# controller.net
KiCad netlist of a schematic drawn in EAGLE
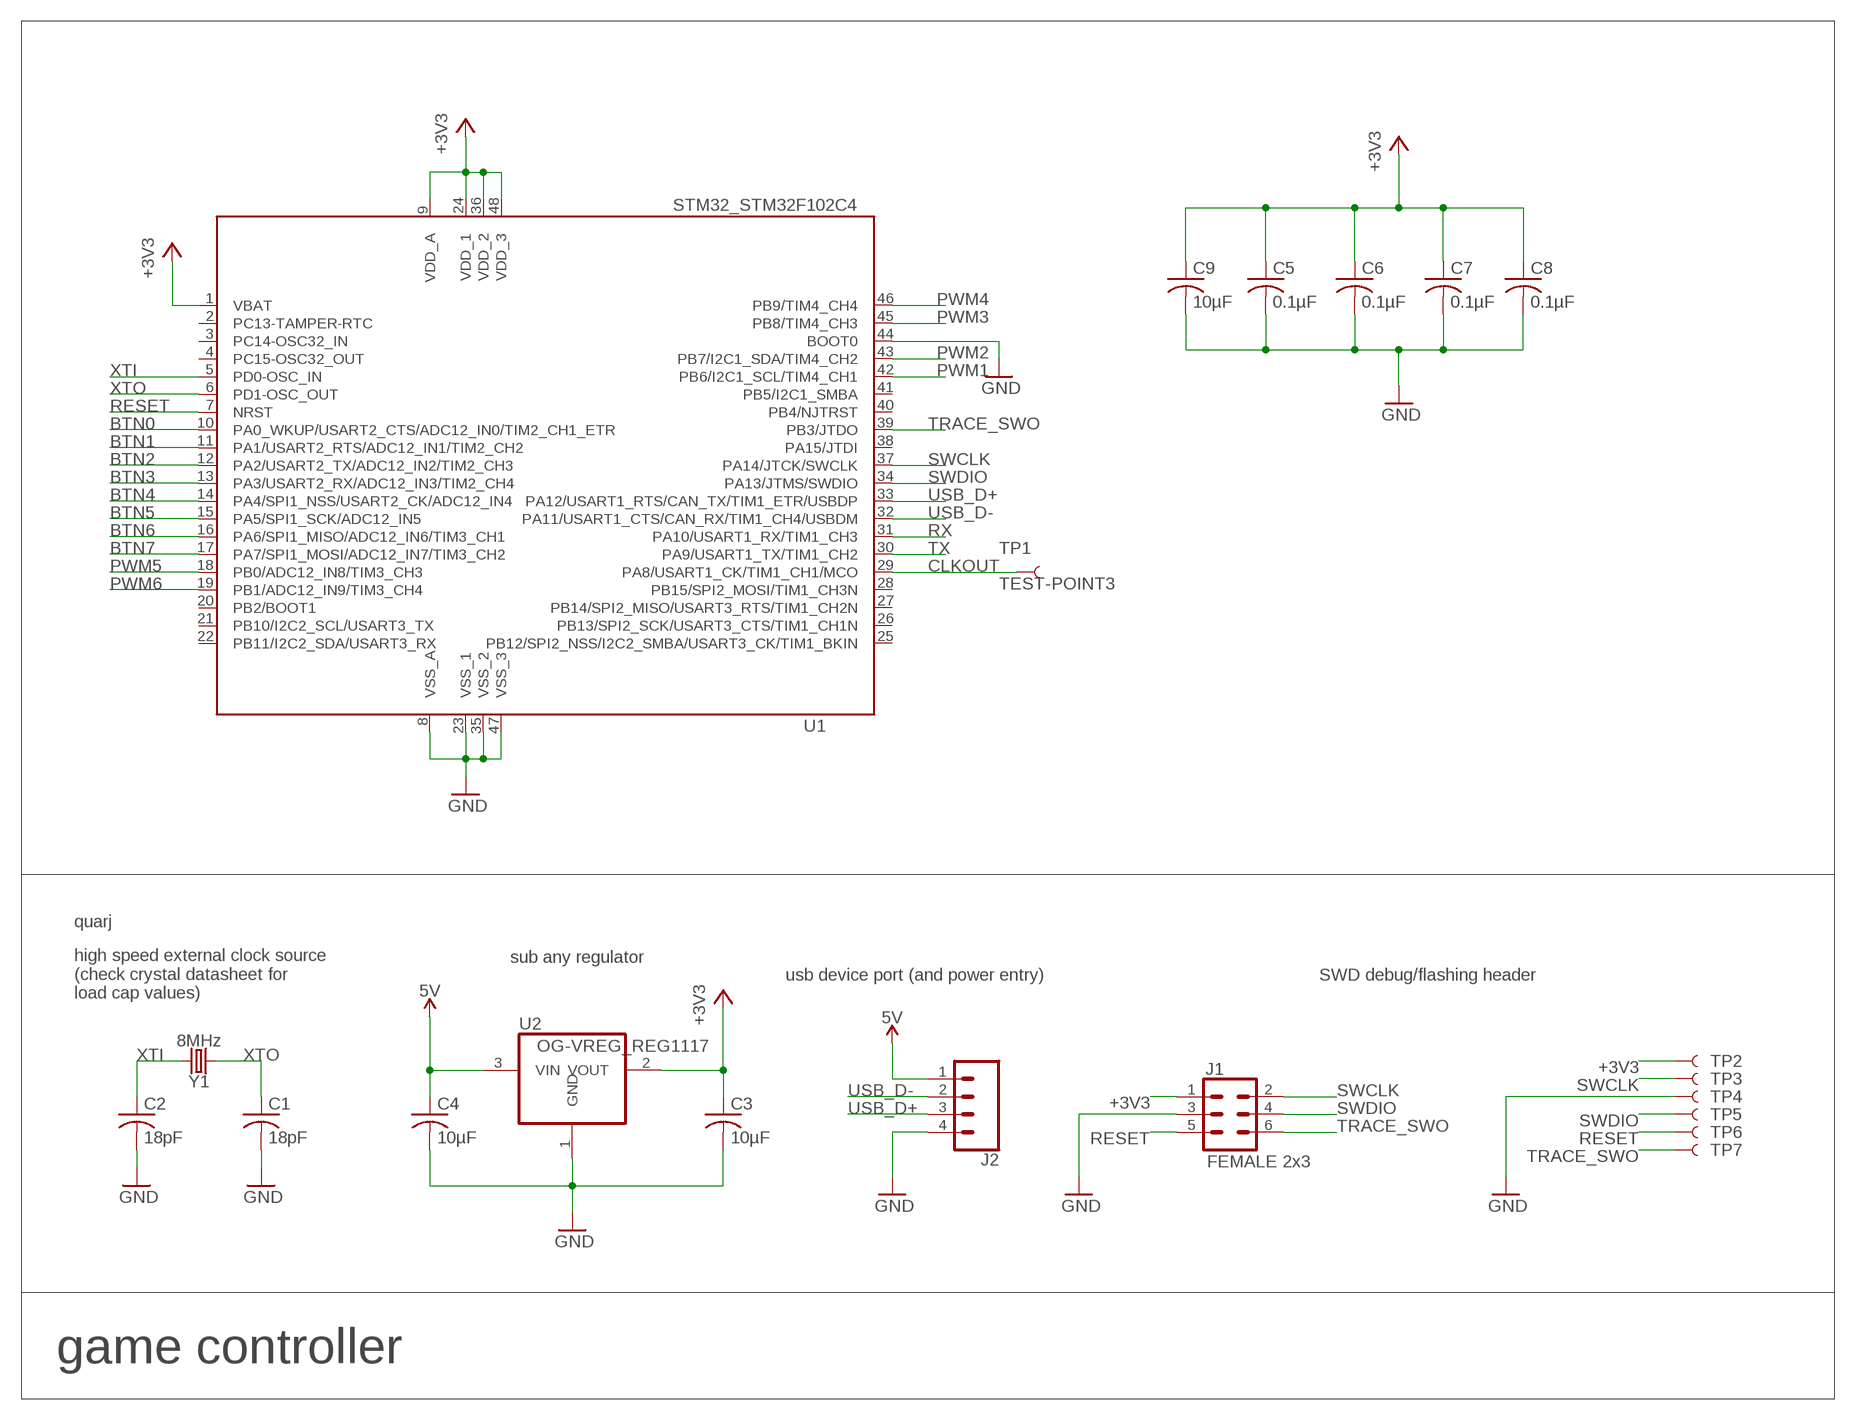
[diagram p0: schematic, sheet 1]
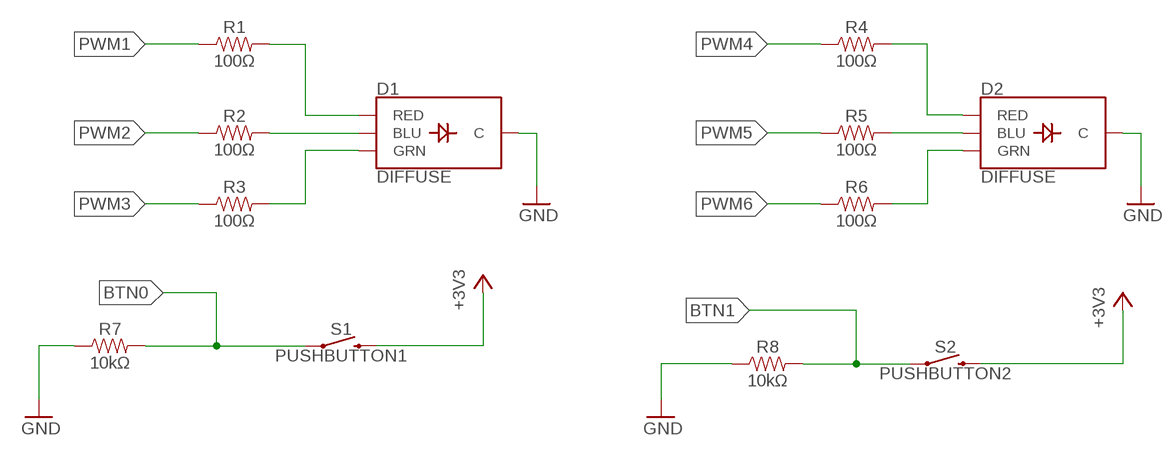
[diagram p1: schematic, sheet 2]
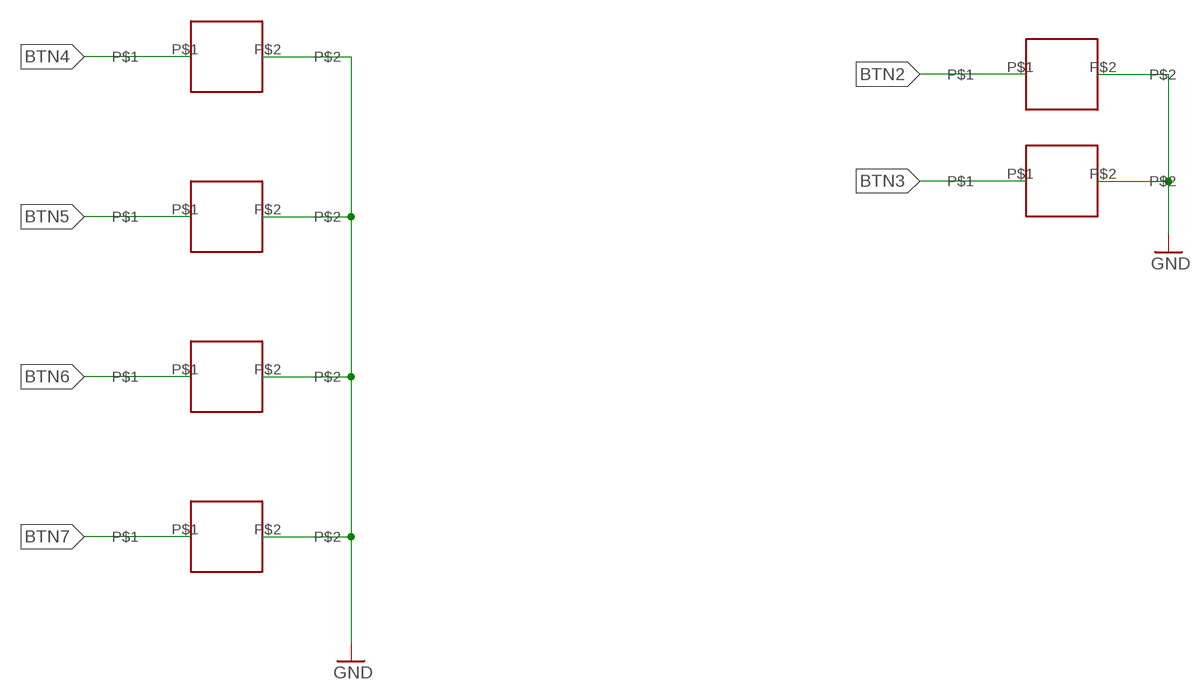
[diagram p2: schematic, sheet 3]

(export (version "E")
  (design (tool "Eeschema 10.0.6"))
  (components
    (comp (ref "A")
      (value "HYPERKIN_TOUCHPAD_CADET")
      (footprint "eagle-import:HYPERKIN_TOUCHPLATE_CADET")
      (libsource (lib "eagle-import") (part "HYPERKIN_TOUCHPAD_CADET"))
    )
    (comp (ref "B")
      (value "HYPERKIN_TOUCHPAD_CADET")
      (footprint "eagle-import:HYPERKIN_TOUCHPLATE_CADET")
      (libsource (lib "eagle-import") (part "HYPERKIN_TOUCHPAD_CADET"))
    )
    (comp (ref "D")
      (value "HYPERKIN_TOUCHPAD_CADET")
      (footprint "eagle-import:HYPERKIN_TOUCHPLATE_CADET")
      (libsource (lib "eagle-import") (part "HYPERKIN_TOUCHPAD_CADET"))
    )
    (comp (ref "L")
      (value "HYPERKIN_TOUCHPAD_CADET")
      (footprint "eagle-import:HYPERKIN_TOUCHPLATE_CADET")
      (libsource (lib "eagle-import") (part "HYPERKIN_TOUCHPAD_CADET"))
    )
    (comp (ref "R")
      (value "HYPERKIN_TOUCHPAD_CADET")
      (footprint "eagle-import:HYPERKIN_TOUCHPLATE_CADET")
      (libsource (lib "eagle-import") (part "HYPERKIN_TOUCHPAD_CADET"))
    )
    (comp (ref "U")
      (value "HYPERKIN_TOUCHPAD_CADET")
      (footprint "eagle-import:HYPERKIN_TOUCHPLATE_CADET")
      (libsource (lib "eagle-import") (part "HYPERKIN_TOUCHPAD_CADET"))
    )
    (comp (ref "D1")
      (value "DIFFUSE")
      (footprint "eagle-import:LED-RGB-THRU")
      (libsource (lib "eagle-import") (part "LED-RGB-CCDIFFUSE"))
    )
    (comp (ref "D2")
      (value "DIFFUSE")
      (footprint "eagle-import:LED-RGB-THRU")
      (libsource (lib "eagle-import") (part "LED-RGB-CCDIFFUSE"))
    )
    (comp (ref "R1")
      (value "100Ω")
      (footprint "eagle-import:0805")
      (libsource (lib "eagle-import") (part "0.3OHM-0805-1/8W-1%"))
    )
    (comp (ref "R2")
      (value "100Ω")
      (footprint "eagle-import:0805")
      (libsource (lib "eagle-import") (part "0.3OHM-0805-1/8W-1%"))
    )
    (comp (ref "R3")
      (value "100Ω")
      (footprint "eagle-import:0805")
      (libsource (lib "eagle-import") (part "0.3OHM-0805-1/8W-1%"))
    )
    (comp (ref "R4")
      (value "100Ω")
      (footprint "eagle-import:0805")
      (libsource (lib "eagle-import") (part "0.3OHM-0805-1/8W-1%"))
    )
    (comp (ref "R5")
      (value "100Ω")
      (footprint "eagle-import:0805")
      (libsource (lib "eagle-import") (part "0.3OHM-0805-1/8W-1%"))
    )
    (comp (ref "R6")
      (value "100Ω")
      (footprint "eagle-import:0805")
      (libsource (lib "eagle-import") (part "0.3OHM-0805-1/8W-1%"))
    )
    (comp (ref "R7")
      (value "10kΩ")
      (footprint "eagle-import:0805")
      (libsource (lib "eagle-import") (part "0.3OHM-0805-1/8W-1%"))
    )
    (comp (ref "R8")
      (value "10kΩ")
      (footprint "eagle-import:0805")
      (libsource (lib "eagle-import") (part "0.3OHM-0805-1/8W-1%"))
    )
    (comp (ref "S1")
      (value "PUSHBUTTON1")
      (footprint "eagle-import:TACTILE_SWITCH_PTH_6.0MM")
      (libsource (lib "eagle-import") (part "MOMENTARY-SWITCH-SPST-PTH-6.0MM"))
    )
    (comp (ref "S2")
      (value "PUSHBUTTON2")
      (footprint "eagle-import:TACTILE_SWITCH_PTH_6.0MM")
      (libsource (lib "eagle-import") (part "MOMENTARY-SWITCH-SPST-PTH-6.0MM"))
    )
    (comp (ref "C1")
      (value "18pF")
      (footprint "eagle-import:RCL_C0805K")
      (libsource (lib "eagle-import") (part "RCL_C-USC0805K"))
    )
    (comp (ref "C2")
      (value "18pF")
      (footprint "eagle-import:RCL_C0805K")
      (libsource (lib "eagle-import") (part "RCL_C-USC0805K"))
    )
    (comp (ref "C3")
      (value "10µF")
      (footprint "eagle-import:RCL_C0805K")
      (libsource (lib "eagle-import") (part "RCL_C-USC0805K"))
    )
    (comp (ref "C4")
      (value "10µF")
      (footprint "eagle-import:RCL_C0805K")
      (libsource (lib "eagle-import") (part "RCL_C-USC0805K"))
    )
    (comp (ref "C5")
      (value "0.1µF")
      (footprint "eagle-import:RCL_C0805K")
      (libsource (lib "eagle-import") (part "RCL_C-USC0805K"))
    )
    (comp (ref "C6")
      (value "0.1µF")
      (footprint "eagle-import:RCL_C0805K")
      (libsource (lib "eagle-import") (part "RCL_C-USC0805K"))
    )
    (comp (ref "C7")
      (value "0.1µF")
      (footprint "eagle-import:RCL_C0805K")
      (libsource (lib "eagle-import") (part "RCL_C-USC0805K"))
    )
    (comp (ref "C8")
      (value "0.1µF")
      (footprint "eagle-import:RCL_C0805K")
      (libsource (lib "eagle-import") (part "RCL_C-USC0805K"))
    )
    (comp (ref "C9")
      (value "10µF")
      (footprint "eagle-import:RCL_C0805K")
      (libsource (lib "eagle-import") (part "RCL_C-USC0805K"))
    )
    (comp (ref "J1")
      (value "FEMALE 2x3")
      (footprint "eagle-import:2X3")
      (libsource (lib "eagle-import") (part "CONN_03X2FEMALE"))
    )
    (comp (ref "J2")
      (value "CONN_04")
      (footprint "eagle-import:1X04")
      (libsource (lib "eagle-import") (part "CONN_04"))
    )
    (comp (ref "TP1")
      (value "TEST-POINT3")
      (footprint "eagle-import:PAD.03X.03")
      (libsource (lib "eagle-import") (part "TEST-POINT3"))
    )
    (comp (ref "TP2")
      (value "TEST-POINT3")
      (footprint "eagle-import:PAD.03X.03")
      (libsource (lib "eagle-import") (part "TEST-POINT3"))
    )
    (comp (ref "TP3")
      (value "TEST-POINT3")
      (footprint "eagle-import:PAD.03X.03")
      (libsource (lib "eagle-import") (part "TEST-POINT3"))
    )
    (comp (ref "TP4")
      (value "TEST-POINT3")
      (footprint "eagle-import:PAD.03X.03")
      (libsource (lib "eagle-import") (part "TEST-POINT3"))
    )
    (comp (ref "TP5")
      (value "TEST-POINT3")
      (footprint "eagle-import:PAD.03X.03")
      (libsource (lib "eagle-import") (part "TEST-POINT3"))
    )
    (comp (ref "TP6")
      (value "TEST-POINT3")
      (footprint "eagle-import:PAD.03X.03")
      (libsource (lib "eagle-import") (part "TEST-POINT3"))
    )
    (comp (ref "TP7")
      (value "TEST-POINT3")
      (footprint "eagle-import:PAD.03X.03")
      (libsource (lib "eagle-import") (part "TEST-POINT3"))
    )
    (comp (ref "U1")
      (value "STM32_STM32F102C4")
      (footprint "eagle-import:STM32_LQFP48")
      (libsource (lib "eagle-import") (part "STM32_STM32F102C4"))
    )
    (comp (ref "U2")
      (value "OG-VREG_REG1117")
      (footprint "eagle-import:OG-VREG_SOT223")
      (libsource (lib "eagle-import") (part "OG-VREG_REG1117"))
    )
    (comp (ref "Y1")
      (value "8MHz")
      (footprint "eagle-import:HC49UP")
      (libsource (lib "eagle-import") (part "CRYSTAL-8MHZSMD-HC49UP"))
    )
  )
  (nets
    (net (code "1") (name "+3V3") (class "Default")
      (node (ref "C3") (pin "1") (pinfunction "1_1") (pintype "passive"))
      (node (ref "C5") (pin "1") (pinfunction "1_1") (pintype "passive"))
      (node (ref "C6") (pin "1") (pinfunction "1_1") (pintype "passive"))
      (node (ref "C7") (pin "1") (pinfunction "1_1") (pintype "passive"))
      (node (ref "C8") (pin "1") (pinfunction "1_1") (pintype "passive"))
      (node (ref "C9") (pin "1") (pinfunction "1_1") (pintype "passive"))
      (node (ref "J1") (pin "1") (pinfunction "1_1") (pintype "bidirectional"))
      (node (ref "S1") (pin "3") (pinfunction "2_3") (pintype "passive"))
      (node (ref "S2") (pin "3") (pinfunction "2_3") (pintype "passive"))
      (node (ref "TP2") (pin "P$1") (pinfunction "1_P$1") (pintype "bidirectional"))
      (node (ref "U1") (pin "1") (pinfunction "VBAT_1") (pintype "power_in"))
      (node (ref "U1") (pin "24") (pinfunction "VDD_1_24") (pintype "power_in"))
      (node (ref "U1") (pin "36") (pinfunction "VDD_2_36") (pintype "power_in"))
      (node (ref "U1") (pin "48") (pinfunction "VDD_3_48") (pintype "power_in"))
      (node (ref "U1") (pin "9") (pinfunction "VDD_A_9") (pintype "power_in"))
      (node (ref "U2") (pin "2") (pinfunction "VOUT_2") (pintype "output"))
    )
    (net (code "2") (name "5V") (class "Default")
      (node (ref "C4") (pin "1") (pinfunction "1_1") (pintype "passive"))
      (node (ref "J2") (pin "1") (pinfunction "1_1") (pintype "passive"))
      (node (ref "U2") (pin "3") (pinfunction "VIN_3") (pintype "input"))
    )
    (net (code "3") (name "BTN0") (class "Default")
      (node (ref "R7") (pin "2") (pinfunction "2_2") (pintype "passive"))
      (node (ref "S1") (pin "1") (pinfunction "1_1") (pintype "passive"))
      (node (ref "U1") (pin "10") (pinfunction "PA0_WKUP/USART2_CTS/ADC12_IN0/TIM2_CH1_ETR_10") (pintype "bidirectional"))
    )
    (net (code "4") (name "BTN1") (class "Default")
      (node (ref "R8") (pin "2") (pinfunction "2_2") (pintype "passive"))
      (node (ref "S2") (pin "1") (pinfunction "1_1") (pintype "passive"))
      (node (ref "U1") (pin "11") (pinfunction "PA1/USART2_RTS/ADC12_IN1/TIM2_CH2_11") (pintype "bidirectional"))
    )
    (net (code "5") (name "BTN2") (class "Default")
      (node (ref "A") (pin "P$1") (pinfunction "P$1_P$1") (pintype "bidirectional"))
      (node (ref "U1") (pin "12") (pinfunction "PA2/USART2_TX/ADC12_IN2/TIM2_CH3_12") (pintype "bidirectional"))
    )
    (net (code "6") (name "BTN3") (class "Default")
      (node (ref "B") (pin "P$1") (pinfunction "P$1_P$1") (pintype "bidirectional"))
      (node (ref "U1") (pin "13") (pinfunction "PA3/USART2_RX/ADC12_IN3/TIM2_CH4_13") (pintype "bidirectional"))
    )
    (net (code "7") (name "BTN4") (class "Default")
      (node (ref "U") (pin "P$1") (pinfunction "P$1_P$1") (pintype "bidirectional"))
      (node (ref "U1") (pin "14") (pinfunction "PA4/SPI1_NSS/USART2_CK/ADC12_IN4_14") (pintype "bidirectional"))
    )
    (net (code "8") (name "BTN5") (class "Default")
      (node (ref "D") (pin "P$1") (pinfunction "P$1_P$1") (pintype "bidirectional"))
      (node (ref "U1") (pin "15") (pinfunction "PA5/SPI1_SCK/ADC12_IN5_15") (pintype "bidirectional"))
    )
    (net (code "9") (name "BTN6") (class "Default")
      (node (ref "L") (pin "P$1") (pinfunction "P$1_P$1") (pintype "bidirectional"))
      (node (ref "U1") (pin "16") (pinfunction "PA6/SPI1_MISO/ADC12_IN6/TIM3_CH1_16") (pintype "bidirectional"))
    )
    (net (code "10") (name "BTN7") (class "Default")
      (node (ref "R") (pin "P$1") (pinfunction "P$1_P$1") (pintype "bidirectional"))
      (node (ref "U1") (pin "17") (pinfunction "PA7/SPI1_MOSI/ADC12_IN7/TIM3_CH2_17") (pintype "bidirectional"))
    )
    (net (code "11") (name "CLKOUT") (class "Default")
      (node (ref "TP1") (pin "P$1") (pinfunction "1_P$1") (pintype "bidirectional"))
      (node (ref "U1") (pin "29") (pinfunction "PA8/USART1_CK/TIM1_CH1/MCO_29") (pintype "bidirectional"))
    )
    (net (code "12") (name "GND") (class "Default")
      (node (ref "A") (pin "P$2") (pinfunction "P$2_P$2") (pintype "bidirectional"))
      (node (ref "B") (pin "P$2") (pinfunction "P$2_P$2") (pintype "bidirectional"))
      (node (ref "C1") (pin "2") (pinfunction "2_2") (pintype "passive"))
      (node (ref "C2") (pin "2") (pinfunction "2_2") (pintype "passive"))
      (node (ref "C3") (pin "2") (pinfunction "2_2") (pintype "passive"))
      (node (ref "C4") (pin "2") (pinfunction "2_2") (pintype "passive"))
      (node (ref "C5") (pin "2") (pinfunction "2_2") (pintype "passive"))
      (node (ref "C6") (pin "2") (pinfunction "2_2") (pintype "passive"))
      (node (ref "C7") (pin "2") (pinfunction "2_2") (pintype "passive"))
      (node (ref "C8") (pin "2") (pinfunction "2_2") (pintype "passive"))
      (node (ref "C9") (pin "2") (pinfunction "2_2") (pintype "passive"))
      (node (ref "D") (pin "P$2") (pinfunction "P$2_P$2") (pintype "bidirectional"))
      (node (ref "D1") (pin "2") (pinfunction "C_2") (pintype "bidirectional"))
      (node (ref "D2") (pin "2") (pinfunction "C_2") (pintype "bidirectional"))
      (node (ref "J1") (pin "3") (pinfunction "3_3") (pintype "bidirectional"))
      (node (ref "J2") (pin "4") (pinfunction "4_4") (pintype "passive"))
      (node (ref "L") (pin "P$2") (pinfunction "P$2_P$2") (pintype "bidirectional"))
      (node (ref "R") (pin "P$2") (pinfunction "P$2_P$2") (pintype "bidirectional"))
      (node (ref "R7") (pin "1") (pinfunction "1_1") (pintype "passive"))
      (node (ref "R8") (pin "1") (pinfunction "1_1") (pintype "passive"))
      (node (ref "TP4") (pin "P$1") (pinfunction "1_P$1") (pintype "bidirectional"))
      (node (ref "U") (pin "P$2") (pinfunction "P$2_P$2") (pintype "bidirectional"))
      (node (ref "U1") (pin "23") (pinfunction "VSS_1_23") (pintype "power_in"))
      (node (ref "U1") (pin "35") (pinfunction "VSS_2_35") (pintype "power_in"))
      (node (ref "U1") (pin "44") (pinfunction "BOOT0_44") (pintype "input"))
      (node (ref "U1") (pin "47") (pinfunction "VSS_3_47") (pintype "power_in"))
      (node (ref "U1") (pin "8") (pinfunction "VSS_A_8") (pintype "power_in"))
      (node (ref "U2") (pin "1") (pinfunction "GND_1") (pintype "power_in"))
    )
    (net (code "13") (name "Net-(D1-BLU)") (class "Default")
      (node (ref "D1") (pin "4") (pinfunction "BLU_4") (pintype "bidirectional"))
      (node (ref "R2") (pin "2") (pinfunction "2_2") (pintype "passive"))
    )
    (net (code "14") (name "Net-(D1-GRN)") (class "Default")
      (node (ref "D1") (pin "3") (pinfunction "GRN_3") (pintype "bidirectional"))
      (node (ref "R3") (pin "2") (pinfunction "2_2") (pintype "passive"))
    )
    (net (code "15") (name "Net-(D1-RED)") (class "Default")
      (node (ref "D1") (pin "1") (pinfunction "RED_1") (pintype "bidirectional"))
      (node (ref "R1") (pin "2") (pinfunction "2_2") (pintype "passive"))
    )
    (net (code "16") (name "Net-(D2-BLU)") (class "Default")
      (node (ref "D2") (pin "4") (pinfunction "BLU_4") (pintype "bidirectional"))
      (node (ref "R5") (pin "2") (pinfunction "2_2") (pintype "passive"))
    )
    (net (code "17") (name "Net-(D2-GRN)") (class "Default")
      (node (ref "D2") (pin "3") (pinfunction "GRN_3") (pintype "bidirectional"))
      (node (ref "R6") (pin "2") (pinfunction "2_2") (pintype "passive"))
    )
    (net (code "18") (name "Net-(D2-RED)") (class "Default")
      (node (ref "D2") (pin "1") (pinfunction "RED_1") (pintype "bidirectional"))
      (node (ref "R4") (pin "2") (pinfunction "2_2") (pintype "passive"))
    )
    (net (code "19") (name "PWM1") (class "Default")
      (node (ref "R1") (pin "1") (pinfunction "1_1") (pintype "passive"))
      (node (ref "U1") (pin "42") (pinfunction "PB6/I2C1_SCL/TIM4_CH1_42") (pintype "input"))
    )
    (net (code "20") (name "PWM2") (class "Default")
      (node (ref "R2") (pin "1") (pinfunction "1_1") (pintype "passive"))
      (node (ref "U1") (pin "43") (pinfunction "PB7/I2C1_SDA/TIM4_CH2_43") (pintype "bidirectional"))
    )
    (net (code "21") (name "PWM3") (class "Default")
      (node (ref "R3") (pin "1") (pinfunction "1_1") (pintype "passive"))
      (node (ref "U1") (pin "45") (pinfunction "PB8/TIM4_CH3_45") (pintype "bidirectional"))
    )
    (net (code "22") (name "PWM4") (class "Default")
      (node (ref "R4") (pin "1") (pinfunction "1_1") (pintype "passive"))
      (node (ref "U1") (pin "46") (pinfunction "PB9/TIM4_CH4_46") (pintype "input"))
    )
    (net (code "23") (name "PWM5") (class "Default")
      (node (ref "R5") (pin "1") (pinfunction "1_1") (pintype "passive"))
      (node (ref "U1") (pin "18") (pinfunction "PB0/ADC12_IN8/TIM3_CH3_18") (pintype "bidirectional"))
    )
    (net (code "24") (name "PWM6") (class "Default")
      (node (ref "R6") (pin "1") (pinfunction "1_1") (pintype "passive"))
      (node (ref "U1") (pin "19") (pinfunction "PB1/ADC12_IN9/TIM3_CH4_19") (pintype "bidirectional"))
    )
    (net (code "25") (name "RESET") (class "Default")
      (node (ref "J1") (pin "5") (pinfunction "5_5") (pintype "bidirectional"))
      (node (ref "TP6") (pin "P$1") (pinfunction "1_P$1") (pintype "bidirectional"))
      (node (ref "U1") (pin "7") (pinfunction "NRST_7") (pintype "input"))
    )
    (net (code "26") (name "RX") (class "Default")
      (node (ref "U1") (pin "31") (pinfunction "PA10/USART1_RX/TIM1_CH3_31") (pintype "bidirectional"))
    )
    (net (code "27") (name "SWCLK") (class "Default")
      (node (ref "J1") (pin "2") (pinfunction "2_2") (pintype "bidirectional"))
      (node (ref "TP3") (pin "P$1") (pinfunction "1_P$1") (pintype "bidirectional"))
      (node (ref "U1") (pin "37") (pinfunction "PA14/JTCK/SWCLK_37") (pintype "bidirectional"))
    )
    (net (code "28") (name "SWDIO") (class "Default")
      (node (ref "J1") (pin "4") (pinfunction "4_4") (pintype "bidirectional"))
      (node (ref "TP5") (pin "P$1") (pinfunction "1_P$1") (pintype "bidirectional"))
      (node (ref "U1") (pin "34") (pinfunction "PA13/JTMS/SWDIO_34") (pintype "bidirectional"))
    )
    (net (code "29") (name "TRACE_SWO") (class "Default")
      (node (ref "J1") (pin "6") (pinfunction "6_6") (pintype "bidirectional"))
      (node (ref "TP7") (pin "P$1") (pinfunction "1_P$1") (pintype "bidirectional"))
      (node (ref "U1") (pin "39") (pinfunction "PB3/JTDO_39") (pintype "bidirectional"))
    )
    (net (code "30") (name "TX") (class "Default")
      (node (ref "U1") (pin "30") (pinfunction "PA9/USART1_TX/TIM1_CH2_30") (pintype "input"))
    )
    (net (code "31") (name "USB_D+") (class "Default")
      (node (ref "J2") (pin "3") (pinfunction "3_3") (pintype "passive"))
      (node (ref "U1") (pin "33") (pinfunction "PA12/USART1_RTS/CAN_TX/TIM1_ETR/USBDP_33") (pintype "bidirectional"))
    )
    (net (code "32") (name "USB_D-") (class "Default")
      (node (ref "J2") (pin "2") (pinfunction "2_2") (pintype "passive"))
      (node (ref "U1") (pin "32") (pinfunction "PA11/USART1_CTS/CAN_RX/TIM1_CH4/USBDM_32") (pintype "bidirectional"))
    )
    (net (code "33") (name "XTI") (class "Default")
      (node (ref "C2") (pin "1") (pinfunction "1_1") (pintype "passive"))
      (node (ref "U1") (pin "5") (pinfunction "PD0-OSC_IN_5") (pintype "input"))
      (node (ref "Y1") (pin "2") (pinfunction "2_2") (pintype "passive"))
    )
    (net (code "34") (name "XTO") (class "Default")
      (node (ref "C1") (pin "1") (pinfunction "1_1") (pintype "passive"))
      (node (ref "U1") (pin "6") (pinfunction "PD1-OSC_OUT_6") (pintype "input"))
      (node (ref "Y1") (pin "1") (pinfunction "1_1") (pintype "passive"))
    )
    (net (code "35") (name "unconnected-(U1-PA15{slash}JTDI-Pad38)") (class "Default")
      (node (ref "U1") (pin "38") (pinfunction "PA15/JTDI_38") (pintype "bidirectional"))
    )
    (net (code "36") (name "unconnected-(U1-PB2{slash}BOOT1-Pad20)") (class "Default")
      (node (ref "U1") (pin "20") (pinfunction "PB2/BOOT1_20") (pintype "bidirectional"))
    )
    (net (code "37") (name "unconnected-(U1-PB4{slash}NJTRST-Pad40)") (class "Default")
      (node (ref "U1") (pin "40") (pinfunction "PB4/NJTRST_40") (pintype "bidirectional"))
    )
    (net (code "38") (name "unconnected-(U1-PB5{slash}I2C1_SMBA-Pad41)") (class "Default")
      (node (ref "U1") (pin "41") (pinfunction "PB5/I2C1_SMBA_41") (pintype "input"))
    )
    (net (code "39") (name "unconnected-(U1-PB10{slash}I2C2_SCL{slash}USART3_TX-Pad21)") (class "Default")
      (node (ref "U1") (pin "21") (pinfunction "PB10/I2C2_SCL/USART3_TX_21") (pintype "input"))
    )
    (net (code "40") (name "unconnected-(U1-PB11{slash}I2C2_SDA{slash}USART3_RX-Pad22)") (class "Default")
      (node (ref "U1") (pin "22") (pinfunction "PB11/I2C2_SDA/USART3_RX_22") (pintype "input"))
    )
    (net (code "41") (name "unconnected-(U1-PB12{slash}SPI2_NSS{slash}I2C2_SMBA{slash}USART3_CK{slash}TIM1_BKIN-Pad25)") (class "Default")
      (node (ref "U1") (pin "25") (pinfunction "PB12/SPI2_NSS/I2C2_SMBA/USART3_CK/TIM1_BKIN_25") (pintype "input"))
    )
    (net (code "42") (name "unconnected-(U1-PB13{slash}SPI2_SCK{slash}USART3_CTS{slash}TIM1_CH1N-Pad26)") (class "Default")
      (node (ref "U1") (pin "26") (pinfunction "PB13/SPI2_SCK/USART3_CTS/TIM1_CH1N_26") (pintype "input"))
    )
    (net (code "43") (name "unconnected-(U1-PB14{slash}SPI2_MISO{slash}USART3_RTS{slash}TIM1_CH2N-Pad27)") (class "Default")
      (node (ref "U1") (pin "27") (pinfunction "PB14/SPI2_MISO/USART3_RTS/TIM1_CH2N_27") (pintype "input"))
    )
    (net (code "44") (name "unconnected-(U1-PB15{slash}SPI2_MOSI{slash}TIM1_CH3N-Pad28)") (class "Default")
      (node (ref "U1") (pin "28") (pinfunction "PB15/SPI2_MOSI/TIM1_CH3N_28") (pintype "input"))
    )
    (net (code "45") (name "unconnected-(U1-PC13-TAMPER-RTC-Pad2)") (class "Default")
      (node (ref "U1") (pin "2") (pinfunction "PC13-TAMPER-RTC_2") (pintype "input"))
    )
    (net (code "46") (name "unconnected-(U1-PC14-OSC32_IN-Pad3)") (class "Default")
      (node (ref "U1") (pin "3") (pinfunction "PC14-OSC32_IN_3") (pintype "input"))
    )
    (net (code "47") (name "unconnected-(U1-PC15-OSC32_OUT-Pad4)") (class "Default")
      (node (ref "U1") (pin "4") (pinfunction "PC15-OSC32_OUT_4") (pintype "input"))
    )
  )
)
